# MotorDriver.net
KiCad netlist of a schematic drawn in Altium Designer
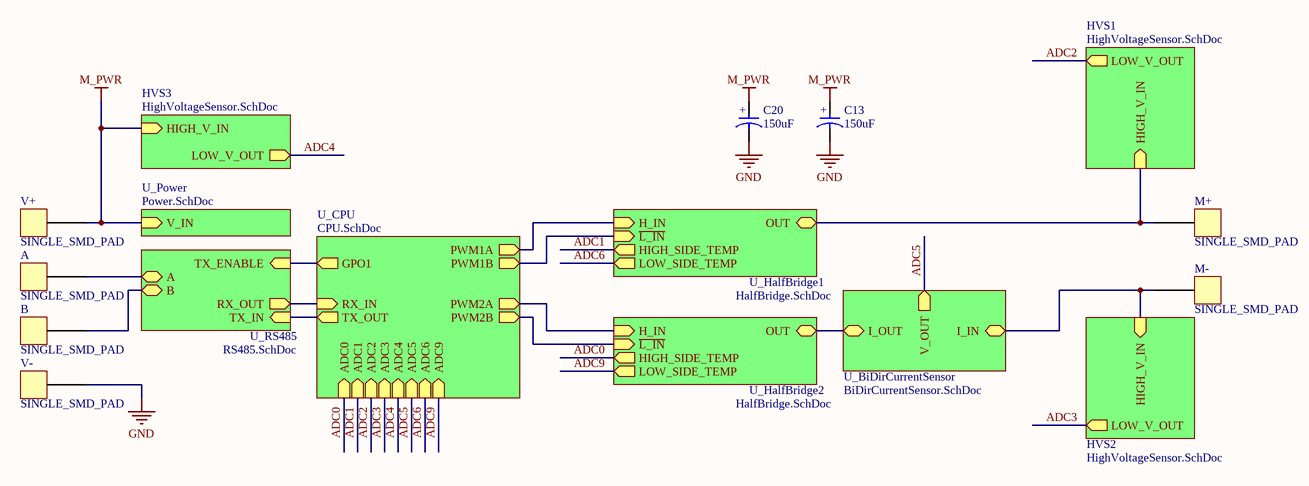
[diagram p0: MotorDriver.SchDoc]

(export (version "E")
  (design (tool "Eeschema 10.0.6"))
  (components
    (comp (ref "A")
      (value "SINGLE_SMD_PAD")
      (footprint "SINGLE_SMD_PAD")
      (libsource (lib "Connectors") (part "SINGLE_SMD_PAD"))
    )
    (comp (ref "B")
      (value "SINGLE_SMD_PAD")
      (footprint "SINGLE_SMD_PAD")
      (libsource (lib "Connectors") (part "SINGLE_SMD_PAD"))
    )
    (comp (ref "C13")
      (value "150uF")
      (footprint "MAL202137151E3")
      (description "CAP ALUM 150UF 40V 20% AXIAL")
      (fields (field (name "Comment") "MAL202137151E3"))
      (libsource (lib "Passives") (part "MAL202137151E3"))
    )
    (comp (ref "C20")
      (value "150uF")
      (footprint "MAL202137151E3")
      (description "CAP ALUM 150UF 40V 20% AXIAL")
      (fields (field (name "Comment") "MAL202137151E3"))
      (libsource (lib "Passives") (part "MAL202137151E3"))
    )
    (comp (ref "M+")
      (value "SINGLE_SMD_PAD")
      (footprint "SINGLE_SMD_PAD")
      (libsource (lib "") (part "SINGLE_SMD_PAD_1"))
    )
    (comp (ref "M-")
      (value "SINGLE_SMD_PAD")
      (footprint "SINGLE_SMD_PAD")
      (libsource (lib "") (part "SINGLE_SMD_PAD_1"))
    )
    (comp (ref "V+")
      (value "SINGLE_SMD_PAD")
      (footprint "SINGLE_SMD_PAD")
      (libsource (lib "Connectors") (part "SINGLE_SMD_PAD"))
    )
    (comp (ref "V-")
      (value "SINGLE_SMD_PAD")
      (footprint "SINGLE_SMD_PAD")
      (libsource (lib "Connectors") (part "SINGLE_SMD_PAD"))
    )
  )
  (nets
    (net (code "1") (name "/A") (class "Default")
      (node (ref "A") (pin "0") (pinfunction "0_0") (pintype "passive"))
    )
    (net (code "10") (name "/B") (class "Default")
      (node (ref "B") (pin "0") (pinfunction "0_0") (pintype "passive"))
    )
    (net (code "12") (name "/HIGH_V_IN") (class "Default")
      (node (ref "M-") (pin "0") (pinfunction "0_0") (pintype "passive"))
    )
    (net (code "13") (name "/HIGH_V_IN_1") (class "Default")
      (node (ref "M+") (pin "0") (pinfunction "0_0") (pintype "passive"))
    )
    (net (code "21") (name "GND") (class "Default")
      (node (ref "C13") (pin "-") (pinfunction "-_-") (pintype "passive"))
      (node (ref "C20") (pin "-") (pinfunction "-_-") (pintype "passive"))
      (node (ref "V-") (pin "0") (pinfunction "0_0") (pintype "passive"))
    )
    (net (code "22") (name "M_PWR") (class "Default")
      (node (ref "C13") (pin "+") (pinfunction "+_+") (pintype "passive"))
      (node (ref "C20") (pin "+") (pinfunction "+_+") (pintype "passive"))
      (node (ref "V+") (pin "0") (pinfunction "0_0") (pintype "passive"))
    )
  )
)
